# Matrix_Platine.net
KiCad netlist of a schematic drawn in EAGLE
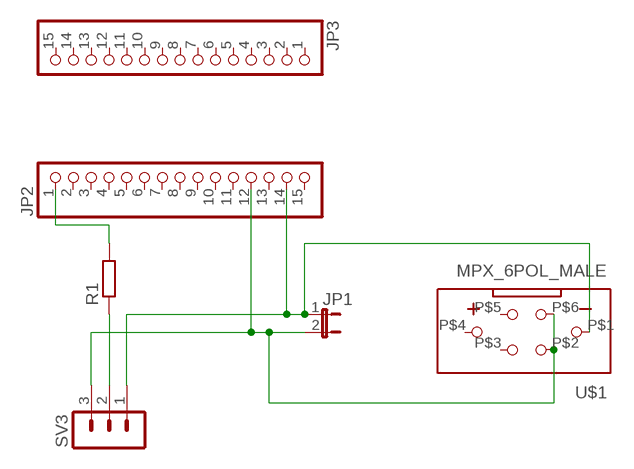
[diagram p0: schematic, sheet 1]

(export (version "E")
  (design (tool "Eeschema 10.0.6"))
  (components
    (comp (ref "JP1")
      (value "JP1E")
      (footprint "eagle-import:JP1")
      (libsource (lib "eagle-import") (part "JP1E"))
    )
    (comp (ref "JP2")
      (value "PINHD-1X15")
      (footprint "eagle-import:1X15")
      (libsource (lib "eagle-import") (part "PINHD-1X15"))
    )
    (comp (ref "JP3")
      (value "PINHD-1X15")
      (footprint "eagle-import:1X15")
      (libsource (lib "eagle-import") (part "PINHD-1X15"))
    )
    (comp (ref "R1")
      (value "R-EU_0204/7")
      (footprint "eagle-import:0204_7")
      (libsource (lib "eagle-import") (part "R-EU_0204/7"))
    )
    (comp (ref "SV3")
      (value "MA03-1")
      (footprint "eagle-import:MA03-1")
      (libsource (lib "eagle-import") (part "MA03-1"))
    )
    (comp (ref "U$1")
      (value "MPX_6POL_MALE")
      (footprint "eagle-import:MPX_MALE")
      (libsource (lib "eagle-import") (part "MPX_6POL_MALE"))
    )
  )
  (nets
    (net (code "1") (name "Net-(JP2-Pad1)") (class "Default")
      (node (ref "JP2") (pin "1") (pinfunction "1_1") (pintype "passive"))
      (node (ref "R1") (pin "2") (pinfunction "2_2") (pintype "passive"))
    )
    (net (code "2") (name "Net-(R1-Pad1)") (class "Default")
      (node (ref "R1") (pin "1") (pinfunction "1_1") (pintype "passive"))
      (node (ref "SV3") (pin "2") (pinfunction "2_2") (pintype "passive"))
    )
    (net (code "3") (name "Net-(U$1-1)") (class "Default")
      (node (ref "JP1") (pin "1") (pinfunction "1_1") (pintype "passive"))
      (node (ref "JP2") (pin "14") (pinfunction "14_14") (pintype "passive"))
      (node (ref "SV3") (pin "1") (pinfunction "1_1") (pintype "passive"))
      (node (ref "U$1") (pin "P$1") (pinfunction "1_P$1") (pintype "passive"))
    )
    (net (code "4") (name "Net-(U$1-2)") (class "Default")
      (node (ref "JP1") (pin "2") (pinfunction "2_2") (pintype "passive"))
      (node (ref "JP2") (pin "12") (pinfunction "12_12") (pintype "passive"))
      (node (ref "SV3") (pin "3") (pinfunction "3_3") (pintype "passive"))
      (node (ref "U$1") (pin "P$2") (pinfunction "2_P$2") (pintype "passive"))
      (node (ref "U$1") (pin "P$6") (pinfunction "6_P$6") (pintype "passive"))
    )
    (net (code "5") (name "unconnected-(JP2-Pad2)") (class "Default")
      (node (ref "JP2") (pin "2") (pinfunction "2_2") (pintype "passive"))
    )
    (net (code "6") (name "unconnected-(JP2-Pad3)") (class "Default")
      (node (ref "JP2") (pin "3") (pinfunction "3_3") (pintype "passive"))
    )
    (net (code "7") (name "unconnected-(JP2-Pad4)") (class "Default")
      (node (ref "JP2") (pin "4") (pinfunction "4_4") (pintype "passive"))
    )
    (net (code "8") (name "unconnected-(JP2-Pad5)") (class "Default")
      (node (ref "JP2") (pin "5") (pinfunction "5_5") (pintype "passive"))
    )
    (net (code "9") (name "unconnected-(JP2-Pad6)") (class "Default")
      (node (ref "JP2") (pin "6") (pinfunction "6_6") (pintype "passive"))
    )
    (net (code "10") (name "unconnected-(JP2-Pad7)") (class "Default")
      (node (ref "JP2") (pin "7") (pinfunction "7_7") (pintype "passive"))
    )
    (net (code "11") (name "unconnected-(JP2-Pad8)") (class "Default")
      (node (ref "JP2") (pin "8") (pinfunction "8_8") (pintype "passive"))
    )
    (net (code "12") (name "unconnected-(JP2-Pad9)") (class "Default")
      (node (ref "JP2") (pin "9") (pinfunction "9_9") (pintype "passive"))
    )
    (net (code "13") (name "unconnected-(JP2-Pad10)") (class "Default")
      (node (ref "JP2") (pin "10") (pinfunction "10_10") (pintype "passive"))
    )
    (net (code "14") (name "unconnected-(JP2-Pad11)") (class "Default")
      (node (ref "JP2") (pin "11") (pinfunction "11_11") (pintype "passive"))
    )
    (net (code "15") (name "unconnected-(JP2-Pad13)") (class "Default")
      (node (ref "JP2") (pin "13") (pinfunction "13_13") (pintype "passive"))
    )
    (net (code "16") (name "unconnected-(JP2-Pad15)") (class "Default")
      (node (ref "JP2") (pin "15") (pinfunction "15_15") (pintype "passive"))
    )
    (net (code "17") (name "unconnected-(JP3-Pad1)") (class "Default")
      (node (ref "JP3") (pin "1") (pinfunction "1_1") (pintype "passive"))
    )
    (net (code "18") (name "unconnected-(JP3-Pad2)") (class "Default")
      (node (ref "JP3") (pin "2") (pinfunction "2_2") (pintype "passive"))
    )
    (net (code "19") (name "unconnected-(JP3-Pad3)") (class "Default")
      (node (ref "JP3") (pin "3") (pinfunction "3_3") (pintype "passive"))
    )
    (net (code "20") (name "unconnected-(JP3-Pad4)") (class "Default")
      (node (ref "JP3") (pin "4") (pinfunction "4_4") (pintype "passive"))
    )
    (net (code "21") (name "unconnected-(JP3-Pad5)") (class "Default")
      (node (ref "JP3") (pin "5") (pinfunction "5_5") (pintype "passive"))
    )
    (net (code "22") (name "unconnected-(JP3-Pad6)") (class "Default")
      (node (ref "JP3") (pin "6") (pinfunction "6_6") (pintype "passive"))
    )
    (net (code "23") (name "unconnected-(JP3-Pad7)") (class "Default")
      (node (ref "JP3") (pin "7") (pinfunction "7_7") (pintype "passive"))
    )
    (net (code "24") (name "unconnected-(JP3-Pad8)") (class "Default")
      (node (ref "JP3") (pin "8") (pinfunction "8_8") (pintype "passive"))
    )
    (net (code "25") (name "unconnected-(JP3-Pad9)") (class "Default")
      (node (ref "JP3") (pin "9") (pinfunction "9_9") (pintype "passive"))
    )
    (net (code "26") (name "unconnected-(JP3-Pad10)") (class "Default")
      (node (ref "JP3") (pin "10") (pinfunction "10_10") (pintype "passive"))
    )
    (net (code "27") (name "unconnected-(JP3-Pad11)") (class "Default")
      (node (ref "JP3") (pin "11") (pinfunction "11_11") (pintype "passive"))
    )
    (net (code "28") (name "unconnected-(JP3-Pad12)") (class "Default")
      (node (ref "JP3") (pin "12") (pinfunction "12_12") (pintype "passive"))
    )
    (net (code "29") (name "unconnected-(JP3-Pad13)") (class "Default")
      (node (ref "JP3") (pin "13") (pinfunction "13_13") (pintype "passive"))
    )
    (net (code "30") (name "unconnected-(JP3-Pad14)") (class "Default")
      (node (ref "JP3") (pin "14") (pinfunction "14_14") (pintype "passive"))
    )
    (net (code "31") (name "unconnected-(JP3-Pad15)") (class "Default")
      (node (ref "JP3") (pin "15") (pinfunction "15_15") (pintype "passive"))
    )
    (net (code "32") (name "unconnected-(U$1-3-PadP$3)") (class "Default")
      (node (ref "U$1") (pin "P$3") (pinfunction "3_P$3") (pintype "passive"))
    )
    (net (code "33") (name "unconnected-(U$1-4-PadP$4)") (class "Default")
      (node (ref "U$1") (pin "P$4") (pinfunction "4_P$4") (pintype "passive"))
    )
    (net (code "34") (name "unconnected-(U$1-5-PadP$5)") (class "Default")
      (node (ref "U$1") (pin "P$5") (pinfunction "5_P$5") (pintype "passive"))
    )
  )
)
